# nand_no_amp.net
KiCad netlist of a schematic drawn in EAGLE
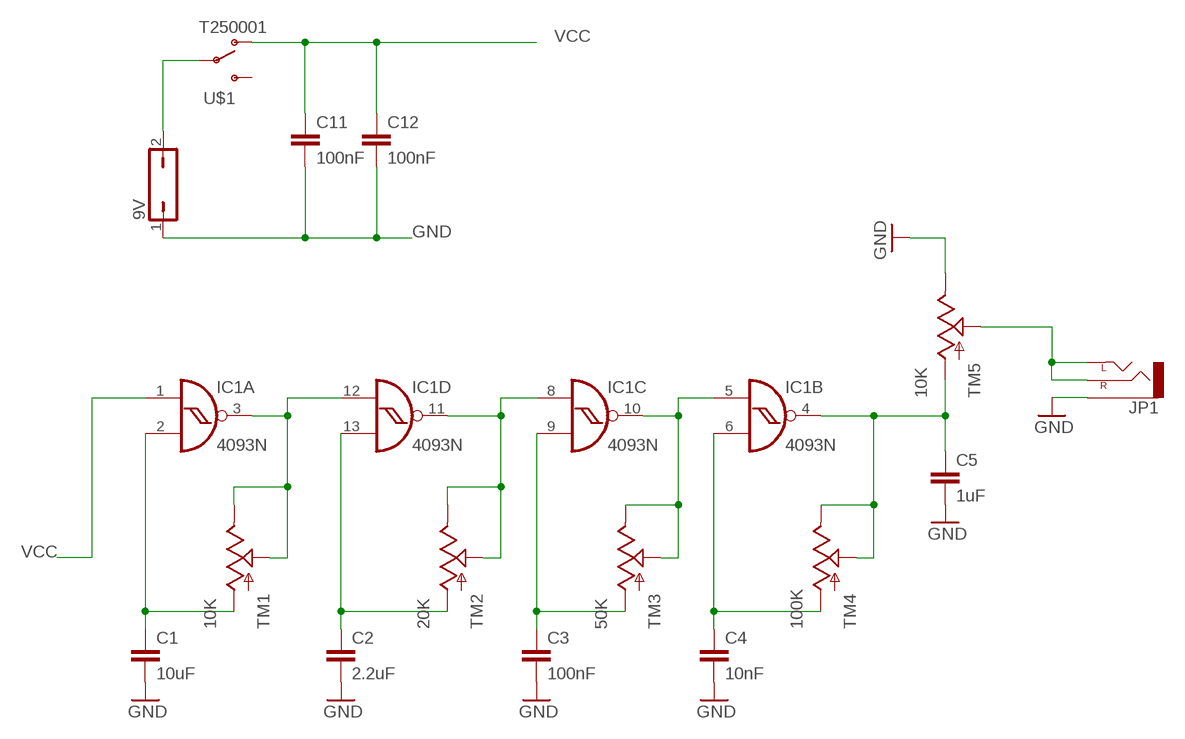
[diagram p0: schematic, sheet 1]

(export (version "E")
  (design (tool "Eeschema 10.0.6"))
  (components
    (comp (ref "9V")
      (value "JP1Q")
      (footprint "eagle-import:JP1")
      (libsource (lib "eagle-import") (part "JP1Q"))
    )
    (comp (ref "C1")
      (value "10uF")
      (footprint "eagle-import:CAP-PTH-5MM")
      (libsource (lib "eagle-import") (part "SparkFun-Passives_CAPPTH1"))
    )
    (comp (ref "C2")
      (value "2.2uF")
      (footprint "eagle-import:CAP-PTH-5MM")
      (libsource (lib "eagle-import") (part "SparkFun-Passives_CAPPTH1"))
    )
    (comp (ref "C3")
      (value "100nF")
      (footprint "eagle-import:CAP-PTH-5MM")
      (libsource (lib "eagle-import") (part "SparkFun-Passives_CAPPTH1"))
    )
    (comp (ref "C4")
      (value "10nF")
      (footprint "eagle-import:CAP-PTH-5MM")
      (libsource (lib "eagle-import") (part "SparkFun-Passives_CAPPTH1"))
    )
    (comp (ref "C5")
      (value "1uF")
      (footprint "eagle-import:CAP-PTH-5MM")
      (libsource (lib "eagle-import") (part "SparkFun-Passives_CAPPTH1"))
    )
    (comp (ref "C11")
      (value "100nF")
      (footprint "eagle-import:CAP-PTH-SMALL")
      (libsource (lib "eagle-import") (part "CAPPTH"))
    )
    (comp (ref "C12")
      (value "100nF")
      (footprint "eagle-import:CAP-PTH-SMALL")
      (libsource (lib "eagle-import") (part "CAPPTH"))
    )
    (comp (ref "IC1")
      (value "4093N")
      (footprint "eagle-import:DIL14")
      (libsource (lib "eagle-import") (part "4093N"))
    )
    (comp (ref "JP1")
      (value "AUDIO-JACKPTH")
      (footprint "eagle-import:AUDIO-JACK")
      (libsource (lib "eagle-import") (part "AUDIO-JACKPTH"))
    )
    (comp (ref "TM1")
      (value "10K")
      (footprint "eagle-import:296SERIESPOT")
      (libsource (lib "eagle-import") (part "296SERIESPOT"))
    )
    (comp (ref "TM2")
      (value "20K")
      (footprint "eagle-import:296SERIESPOT")
      (libsource (lib "eagle-import") (part "296SERIESPOT"))
    )
    (comp (ref "TM3")
      (value "50K")
      (footprint "eagle-import:296SERIESPOT")
      (libsource (lib "eagle-import") (part "296SERIESPOT"))
    )
    (comp (ref "TM4")
      (value "100K")
      (footprint "eagle-import:296SERIESPOT")
      (libsource (lib "eagle-import") (part "296SERIESPOT"))
    )
    (comp (ref "TM5")
      (value "10K")
      (footprint "eagle-import:296SERIESPOT")
      (libsource (lib "eagle-import") (part "296SERIESPOT"))
    )
    (comp (ref "U$1")
      (value "T250001")
      (footprint "eagle-import:T250001")
      (libsource (lib "eagle-import") (part "T250001"))
    )
  )
  (nets
    (net (code "1") (name "/VCC") (class "Default")
      (node (ref "C11") (pin "1") (pinfunction "1_1") (pintype "passive"))
      (node (ref "C12") (pin "1") (pinfunction "1_1") (pintype "passive"))
      (node (ref "IC1") (pin "1") (pinfunction "I0_1") (pintype "input"))
      (node (ref "U$1") (pin "4") (pinfunction "O_4") (pintype "passive"))
    )
    (net (code "2") (name "GND") (class "Default")
      (node (ref "9V") (pin "1") (pinfunction "1_1") (pintype "passive"))
      (node (ref "C1") (pin "2") (pinfunction "2_2") (pintype "passive"))
      (node (ref "C11") (pin "2") (pinfunction "2_2") (pintype "passive"))
      (node (ref "C12") (pin "2") (pinfunction "2_2") (pintype "passive"))
      (node (ref "C2") (pin "2") (pinfunction "2_2") (pintype "passive"))
      (node (ref "C3") (pin "2") (pinfunction "2_2") (pintype "passive"))
      (node (ref "C4") (pin "2") (pinfunction "2_2") (pintype "passive"))
      (node (ref "C5") (pin "2") (pinfunction "2_2") (pintype "passive"))
      (node (ref "JP1") (pin "SLEEVE") (pinfunction "SLEEVE_SLEEVE") (pintype "bidirectional"))
      (node (ref "TM5") (pin "PIN3") (pinfunction "E_PIN3") (pintype "passive"))
    )
    (net (code "3") (name "Net-(IC1A-I1)") (class "Default")
      (node (ref "C1") (pin "1") (pinfunction "1_1") (pintype "passive"))
      (node (ref "IC1") (pin "2") (pinfunction "I1_2") (pintype "input"))
      (node (ref "TM1") (pin "PIN1") (pinfunction "A_PIN1") (pintype "passive"))
    )
    (net (code "4") (name "Net-(IC1A-O)") (class "Default")
      (node (ref "IC1") (pin "12") (pinfunction "I0_12") (pintype "input"))
      (node (ref "IC1") (pin "3") (pinfunction "O_3") (pintype "output"))
      (node (ref "TM1") (pin "PIN2") (pinfunction "S_PIN2") (pintype "passive"))
      (node (ref "TM1") (pin "PIN3") (pinfunction "E_PIN3") (pintype "passive"))
    )
    (net (code "5") (name "Net-(IC1B-I0)") (class "Default")
      (node (ref "IC1") (pin "10") (pinfunction "O_10") (pintype "output"))
      (node (ref "IC1") (pin "5") (pinfunction "I0_5") (pintype "input"))
      (node (ref "TM3") (pin "PIN2") (pinfunction "S_PIN2") (pintype "passive"))
      (node (ref "TM3") (pin "PIN3") (pinfunction "E_PIN3") (pintype "passive"))
    )
    (net (code "6") (name "Net-(IC1B-I1)") (class "Default")
      (node (ref "C4") (pin "1") (pinfunction "1_1") (pintype "passive"))
      (node (ref "IC1") (pin "6") (pinfunction "I1_6") (pintype "input"))
      (node (ref "TM4") (pin "PIN1") (pinfunction "A_PIN1") (pintype "passive"))
    )
    (net (code "7") (name "Net-(IC1B-O)") (class "Default")
      (node (ref "C5") (pin "1") (pinfunction "1_1") (pintype "passive"))
      (node (ref "IC1") (pin "4") (pinfunction "O_4") (pintype "output"))
      (node (ref "TM4") (pin "PIN2") (pinfunction "S_PIN2") (pintype "passive"))
      (node (ref "TM4") (pin "PIN3") (pinfunction "E_PIN3") (pintype "passive"))
      (node (ref "TM5") (pin "PIN1") (pinfunction "A_PIN1") (pintype "passive"))
    )
    (net (code "8") (name "Net-(IC1C-I0)") (class "Default")
      (node (ref "IC1") (pin "11") (pinfunction "O_11") (pintype "output"))
      (node (ref "IC1") (pin "8") (pinfunction "I0_8") (pintype "input"))
      (node (ref "TM2") (pin "PIN2") (pinfunction "S_PIN2") (pintype "passive"))
      (node (ref "TM2") (pin "PIN3") (pinfunction "E_PIN3") (pintype "passive"))
    )
    (net (code "9") (name "Net-(IC1C-I1)") (class "Default")
      (node (ref "C3") (pin "1") (pinfunction "1_1") (pintype "passive"))
      (node (ref "IC1") (pin "9") (pinfunction "I1_9") (pintype "input"))
      (node (ref "TM3") (pin "PIN1") (pinfunction "A_PIN1") (pintype "passive"))
    )
    (net (code "10") (name "Net-(IC1D-I1)") (class "Default")
      (node (ref "C2") (pin "1") (pinfunction "1_1") (pintype "passive"))
      (node (ref "IC1") (pin "13") (pinfunction "I1_13") (pintype "input"))
      (node (ref "TM2") (pin "PIN1") (pinfunction "A_PIN1") (pintype "passive"))
    )
    (net (code "11") (name "Net-(JP1-LEFT)") (class "Default")
      (node (ref "JP1") (pin "RING") (pinfunction "RIGHT_RING") (pintype "bidirectional"))
      (node (ref "JP1") (pin "TIP") (pinfunction "LEFT_TIP") (pintype "bidirectional"))
      (node (ref "TM5") (pin "PIN2") (pinfunction "S_PIN2") (pintype "passive"))
    )
    (net (code "12") (name "Net-(U$1-P)") (class "Default")
      (node (ref "9V") (pin "2") (pinfunction "2_2") (pintype "passive"))
      (node (ref "U$1") (pin "5") (pinfunction "P_5") (pintype "passive"))
    )
    (net (code "13") (name "unconnected-(U$1-S-Pad6)") (class "Default")
      (node (ref "U$1") (pin "6") (pinfunction "S_6") (pintype "passive"))
    )
  )
)
